# other.net
KiCad netlist of a schematic drawn in Altium Designer
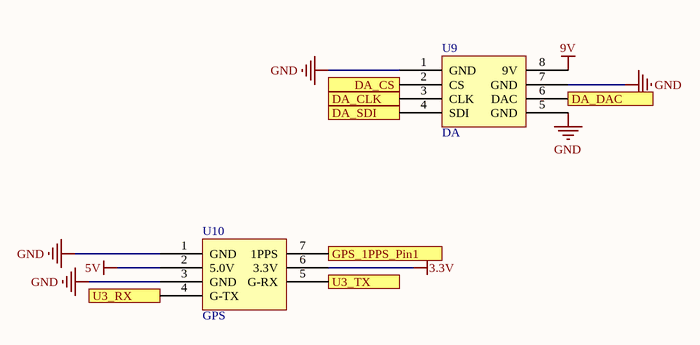
[diagram p0: other.SchDoc]

(export (version "E")
  (design (tool "Eeschema 10.0.6"))
  (components
    (comp (ref "U9") (value "DA") (footprint "DA") (libsource (lib "MyLib") (part "DA")))
    (comp (ref "U10") (value "GPS") (footprint "GPS") (libsource (lib "MyLib") (part "GPS")))
  )
  (nets
    (net (code "1") (name "/DA_CLK") (class "Default")
      (node (ref "U9") (pin "3") (pinfunction "CLK_3") (pintype "passive"))
    )
    (net (code "2") (name "/DA_CS") (class "Default")
      (node (ref "U9") (pin "2") (pinfunction "CS_2") (pintype "passive"))
    )
    (net (code "3") (name "/DA_DAC") (class "Default")
      (node (ref "U9") (pin "6") (pinfunction "DAC_6") (pintype "passive"))
    )
    (net (code "4") (name "/DA_SDI") (class "Default")
      (node (ref "U9") (pin "4") (pinfunction "SDI_4") (pintype "passive"))
    )
    (net (code "5") (name "/GPS_1PPS_Pin1") (class "Default")
      (node (ref "U10") (pin "7") (pinfunction "1PPS_7") (pintype "passive"))
    )
    (net (code "6") (name "/U3_RX") (class "Default")
      (node (ref "U10") (pin "4") (pinfunction "G-TX_4") (pintype "passive"))
    )
    (net (code "7") (name "/U3_TX") (class "Default")
      (node (ref "U10") (pin "5") (pinfunction "G-RX_5") (pintype "passive"))
    )
    (net (code "8") (name "3.3V") (class "Default")
      (node (ref "U10") (pin "6") (pinfunction "3.3V_6") (pintype "passive"))
    )
    (net (code "9") (name "5V") (class "Default")
      (node (ref "U10") (pin "2") (pinfunction "5.0V_2") (pintype "passive"))
    )
    (net (code "10") (name "9V") (class "Default")
      (node (ref "U9") (pin "8") (pinfunction "9V_8") (pintype "passive"))
    )
    (net (code "11") (name "GND") (class "Default")
      (node (ref "U10") (pin "1") (pinfunction "GND_1") (pintype "passive"))
      (node (ref "U10") (pin "3") (pinfunction "GND_3") (pintype "passive"))
      (node (ref "U9") (pin "1") (pinfunction "GND_1") (pintype "passive"))
      (node (ref "U9") (pin "5") (pinfunction "GND_5") (pintype "passive"))
      (node (ref "U9") (pin "7") (pinfunction "GND_7") (pintype "passive"))
    )
  )
)
